# Amplifier_Board.net
KiCad netlist of a schematic drawn in Altium Designer
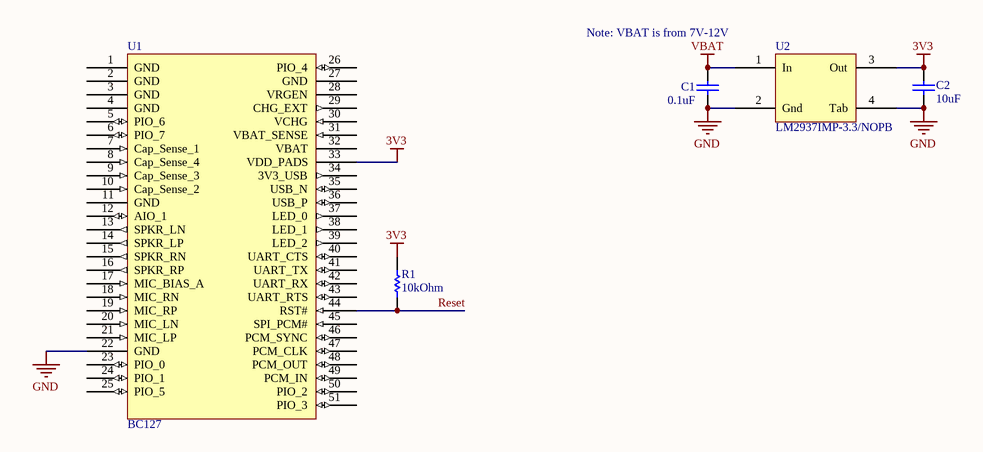
[diagram p0: Amplifier Board.SchDoc]

(export (version "E")
  (design (tool "Eeschema 10.0.6"))
  (components
    (comp (ref "C1")
      (value "0.1uF")
      (footprint "C1206")
      (description "Regulator Filter Cap")
      (fields (field (name "PUBLISHER") "Altium Limited"))
      (libsource (lib "Miscellaneous Devices") (part "Cap Semi"))
    )
    (comp (ref "C2")
      (value "10uF")
      (footprint "C1206")
      (description "1206 Ceramic Capacitor")
      (fields (field (name "PUBLISHER") "Altium Limited"))
      (libsource (lib "Miscellaneous Devices") (part "Cap Semi"))
    )
    (comp (ref "R1")
      (value "10kOhm")
      (footprint "RESC0603(1608)_N")
      (description "0603 10K Resistor")
      (fields (field (name "POWER") "None"))
      (libsource (lib "Altium Content Vault") (part "CMP-1012-00001-1"))
    )
    (comp (ref "U1")
      (value "BC127")
      (footprint "BC127")
      (description "Bluetooth Module")
      (libsource (lib "Speaker Library") (part "BC127"))
    )
    (comp (ref "U2")
      (value "LM2937IMP-3.3/NOPB")
      (footprint "DSO-G3/C6.4")
      (libsource (lib "Speaker Library") (part "LM2937IMP-3.3/NOPB"))
    )
  )
  (nets
    (net (code "1") (name "/Reset") (class "Default")
      (node (ref "R1") (pin "1") (pinfunction "1_1") (pintype "passive"))
      (node (ref "U1") (pin "44") (pinfunction "RST#_44") (pintype "input"))
    )
    (net (code "2") (name "3V3") (class "Default")
      (node (ref "C2") (pin "2") (pinfunction "2_2") (pintype "passive"))
      (node (ref "R1") (pin "2") (pinfunction "2_2") (pintype "passive"))
      (node (ref "U1") (pin "33") (pinfunction "VDD_PADS_33") (pintype "power_in"))
      (node (ref "U2") (pin "3") (pinfunction "Out_3") (pintype "power_in"))
    )
    (net (code "3") (name "GND") (class "Default")
      (node (ref "C1") (pin "1") (pinfunction "1_1") (pintype "passive"))
      (node (ref "C2") (pin "1") (pinfunction "1_1") (pintype "passive"))
      (node (ref "U1") (pin "22") (pinfunction "GND_22") (pintype "power_in"))
      (node (ref "U2") (pin "2") (pinfunction "Gnd_2") (pintype "power_in"))
      (node (ref "U2") (pin "4") (pinfunction "Tab_4") (pintype "power_in"))
    )
    (net (code "4") (name "VBAT") (class "Default")
      (node (ref "C1") (pin "2") (pinfunction "2_2") (pintype "passive"))
      (node (ref "U2") (pin "1") (pinfunction "In_1") (pintype "power_in"))
    )
    (net (code "5") (name "unconnected-(U1-3V3_USB-Pad34)") (class "Default")
      (node (ref "U1") (pin "34") (pinfunction "3V3_USB_34") (pintype "output"))
    )
    (net (code "6") (name "unconnected-(U1-AIO_1-Pad12)") (class "Default")
      (node (ref "U1") (pin "12") (pinfunction "AIO_1_12") (pintype "bidirectional"))
    )
    (net (code "7") (name "unconnected-(U1-CHG_EXT-Pad29)") (class "Default")
      (node (ref "U1") (pin "29") (pinfunction "CHG_EXT_29") (pintype "output"))
    )
    (net (code "8") (name "unconnected-(U1-Cap_Sense_1-Pad7)") (class "Default")
      (node (ref "U1") (pin "7") (pinfunction "Cap_Sense_1_7") (pintype "input"))
    )
    (net (code "9") (name "unconnected-(U1-Cap_Sense_2-Pad10)") (class "Default")
      (node (ref "U1") (pin "10") (pinfunction "Cap_Sense_2_10") (pintype "input"))
    )
    (net (code "10") (name "unconnected-(U1-Cap_Sense_3-Pad9)") (class "Default")
      (node (ref "U1") (pin "9") (pinfunction "Cap_Sense_3_9") (pintype "input"))
    )
    (net (code "11") (name "unconnected-(U1-Cap_Sense_4-Pad8)") (class "Default")
      (node (ref "U1") (pin "8") (pinfunction "Cap_Sense_4_8") (pintype "input"))
    )
    (net (code "12") (name "unconnected-(U1-GND-Pad1)") (class "Default")
      (node (ref "U1") (pin "1") (pinfunction "GND_1") (pintype "power_in"))
    )
    (net (code "13") (name "unconnected-(U1-GND-Pad2)") (class "Default")
      (node (ref "U1") (pin "2") (pinfunction "GND_2") (pintype "power_in"))
    )
    (net (code "14") (name "unconnected-(U1-GND-Pad3)") (class "Default")
      (node (ref "U1") (pin "3") (pinfunction "GND_3") (pintype "power_in"))
    )
    (net (code "15") (name "unconnected-(U1-GND-Pad4)") (class "Default")
      (node (ref "U1") (pin "4") (pinfunction "GND_4") (pintype "power_in"))
    )
    (net (code "16") (name "unconnected-(U1-GND-Pad11)") (class "Default")
      (node (ref "U1") (pin "11") (pinfunction "GND_11") (pintype "power_in"))
    )
    (net (code "17") (name "unconnected-(U1-GND-Pad27)") (class "Default")
      (node (ref "U1") (pin "27") (pinfunction "GND_27") (pintype "power_in"))
    )
    (net (code "18") (name "unconnected-(U1-LED_0-Pad37)") (class "Default")
      (node (ref "U1") (pin "37") (pinfunction "LED_0_37") (pintype "output"))
    )
    (net (code "19") (name "unconnected-(U1-LED_1-Pad38)") (class "Default")
      (node (ref "U1") (pin "38") (pinfunction "LED_1_38") (pintype "output"))
    )
    (net (code "20") (name "unconnected-(U1-LED_2-Pad39)") (class "Default")
      (node (ref "U1") (pin "39") (pinfunction "LED_2_39") (pintype "output"))
    )
    (net (code "21") (name "unconnected-(U1-MIC_BIAS_A-Pad17)") (class "Default")
      (node (ref "U1") (pin "17") (pinfunction "MIC_BIAS_A_17") (pintype "input"))
    )
    (net (code "22") (name "unconnected-(U1-MIC_LN-Pad20)") (class "Default")
      (node (ref "U1") (pin "20") (pinfunction "MIC_LN_20") (pintype "input"))
    )
    (net (code "23") (name "unconnected-(U1-MIC_LP-Pad21)") (class "Default")
      (node (ref "U1") (pin "21") (pinfunction "MIC_LP_21") (pintype "input"))
    )
    (net (code "24") (name "unconnected-(U1-MIC_RN-Pad18)") (class "Default")
      (node (ref "U1") (pin "18") (pinfunction "MIC_RN_18") (pintype "input"))
    )
    (net (code "25") (name "unconnected-(U1-MIC_RP-Pad19)") (class "Default")
      (node (ref "U1") (pin "19") (pinfunction "MIC_RP_19") (pintype "input"))
    )
    (net (code "26") (name "unconnected-(U1-PCM_CLK-Pad47)") (class "Default")
      (node (ref "U1") (pin "47") (pinfunction "PCM_CLK_47") (pintype "bidirectional"))
    )
    (net (code "27") (name "unconnected-(U1-PCM_IN-Pad49)") (class "Default")
      (node (ref "U1") (pin "49") (pinfunction "PCM_IN_49") (pintype "bidirectional"))
    )
    (net (code "28") (name "unconnected-(U1-PCM_OUT-Pad48)") (class "Default")
      (node (ref "U1") (pin "48") (pinfunction "PCM_OUT_48") (pintype "bidirectional"))
    )
    (net (code "29") (name "unconnected-(U1-PCM_SYNC-Pad46)") (class "Default")
      (node (ref "U1") (pin "46") (pinfunction "PCM_SYNC_46") (pintype "bidirectional"))
    )
    (net (code "30") (name "unconnected-(U1-PIO_0-Pad23)") (class "Default")
      (node (ref "U1") (pin "23") (pinfunction "PIO_0_23") (pintype "bidirectional"))
    )
    (net (code "31") (name "unconnected-(U1-PIO_1-Pad24)") (class "Default")
      (node (ref "U1") (pin "24") (pinfunction "PIO_1_24") (pintype "bidirectional"))
    )
    (net (code "32") (name "unconnected-(U1-PIO_2-Pad50)") (class "Default")
      (node (ref "U1") (pin "50") (pinfunction "PIO_2_50") (pintype "bidirectional"))
    )
    (net (code "33") (name "unconnected-(U1-PIO_3-Pad51)") (class "Default")
      (node (ref "U1") (pin "51") (pinfunction "PIO_3_51") (pintype "bidirectional"))
    )
    (net (code "34") (name "unconnected-(U1-PIO_4-Pad26)") (class "Default")
      (node (ref "U1") (pin "26") (pinfunction "PIO_4_26") (pintype "bidirectional"))
    )
    (net (code "35") (name "unconnected-(U1-PIO_5-Pad25)") (class "Default")
      (node (ref "U1") (pin "25") (pinfunction "PIO_5_25") (pintype "bidirectional"))
    )
    (net (code "36") (name "unconnected-(U1-PIO_6-Pad5)") (class "Default")
      (node (ref "U1") (pin "5") (pinfunction "PIO_6_5") (pintype "bidirectional"))
    )
    (net (code "37") (name "unconnected-(U1-PIO_7-Pad6)") (class "Default")
      (node (ref "U1") (pin "6") (pinfunction "PIO_7_6") (pintype "bidirectional"))
    )
    (net (code "38") (name "unconnected-(U1-SPI_PCM#-Pad45)") (class "Default")
      (node (ref "U1") (pin "45") (pinfunction "SPI_PCM#_45") (pintype "input"))
    )
    (net (code "39") (name "unconnected-(U1-SPKR_LN-Pad13)") (class "Default")
      (node (ref "U1") (pin "13") (pinfunction "SPKR_LN_13") (pintype "output"))
    )
    (net (code "40") (name "unconnected-(U1-SPKR_LP-Pad14)") (class "Default")
      (node (ref "U1") (pin "14") (pinfunction "SPKR_LP_14") (pintype "output"))
    )
    (net (code "41") (name "unconnected-(U1-SPKR_RN-Pad15)") (class "Default")
      (node (ref "U1") (pin "15") (pinfunction "SPKR_RN_15") (pintype "output"))
    )
    (net (code "42") (name "unconnected-(U1-SPKR_RP-Pad16)") (class "Default")
      (node (ref "U1") (pin "16") (pinfunction "SPKR_RP_16") (pintype "output"))
    )
    (net (code "43") (name "unconnected-(U1-UART_CTS-Pad40)") (class "Default")
      (node (ref "U1") (pin "40") (pinfunction "UART_CTS_40") (pintype "bidirectional"))
    )
    (net (code "44") (name "unconnected-(U1-UART_RTS-Pad43)") (class "Default")
      (node (ref "U1") (pin "43") (pinfunction "UART_RTS_43") (pintype "bidirectional"))
    )
    (net (code "45") (name "unconnected-(U1-UART_RX-Pad42)") (class "Default")
      (node (ref "U1") (pin "42") (pinfunction "UART_RX_42") (pintype "bidirectional"))
    )
    (net (code "46") (name "unconnected-(U1-UART_TX-Pad41)") (class "Default")
      (node (ref "U1") (pin "41") (pinfunction "UART_TX_41") (pintype "bidirectional"))
    )
    (net (code "47") (name "unconnected-(U1-USB_N-Pad35)") (class "Default")
      (node (ref "U1") (pin "35") (pinfunction "USB_N_35") (pintype "bidirectional"))
    )
    (net (code "48") (name "unconnected-(U1-USB_P-Pad36)") (class "Default")
      (node (ref "U1") (pin "36") (pinfunction "USB_P_36") (pintype "bidirectional"))
    )
    (net (code "49") (name "unconnected-(U1-VBAT-Pad32)") (class "Default")
      (node (ref "U1") (pin "32") (pinfunction "VBAT_32") (pintype "passive"))
    )
    (net (code "50") (name "unconnected-(U1-VBAT_SENSE-Pad31)") (class "Default")
      (node (ref "U1") (pin "31") (pinfunction "VBAT_SENSE_31") (pintype "input"))
    )
    (net (code "51") (name "unconnected-(U1-VCHG-Pad30)") (class "Default")
      (node (ref "U1") (pin "30") (pinfunction "VCHG_30") (pintype "input"))
    )
    (net (code "52") (name "unconnected-(U1-VRGEN-Pad28)") (class "Default")
      (node (ref "U1") (pin "28") (pinfunction "VRGEN_28") (pintype "passive"))
    )
  )
)
